# arduino-dice.net
KiCad netlist of a schematic drawn in EAGLE
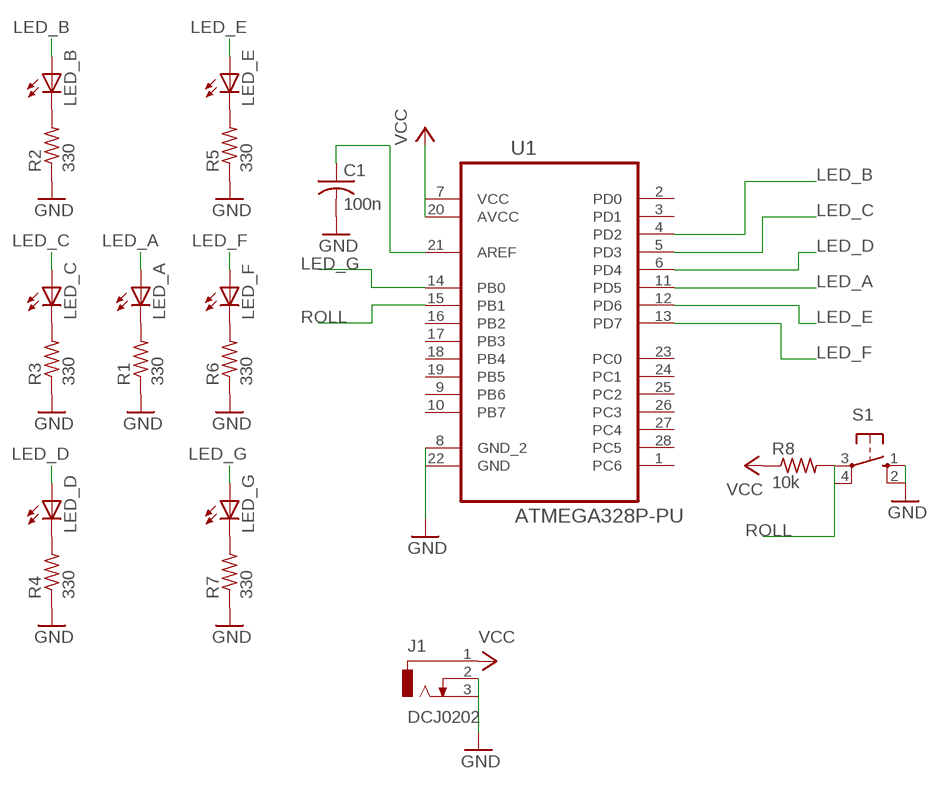
[diagram p0: schematic, sheet 1]

(export (version "E")
  (design (tool "Eeschema 10.0.6"))
  (components
    (comp (ref "C1")
      (value "100n")
      (footprint "eagle-import:C050-024X044")
      (libsource (lib "eagle-import") (part "C-US050-024X044"))
    )
    (comp (ref "J1")
      (value "DCJ0202")
      (footprint "eagle-import:DCJ0202")
      (libsource (lib "eagle-import") (part "DCJ0202"))
    )
    (comp (ref "LED_A")
      (value "LED5MM")
      (footprint "eagle-import:LED5MM")
      (libsource (lib "eagle-import") (part "LED5MM"))
    )
    (comp (ref "LED_B")
      (value "LED5MM")
      (footprint "eagle-import:LED5MM")
      (libsource (lib "eagle-import") (part "LED5MM"))
    )
    (comp (ref "LED_C")
      (value "LED5MM")
      (footprint "eagle-import:LED5MM")
      (libsource (lib "eagle-import") (part "LED5MM"))
    )
    (comp (ref "LED_D")
      (value "LED5MM")
      (footprint "eagle-import:LED5MM")
      (libsource (lib "eagle-import") (part "LED5MM"))
    )
    (comp (ref "LED_E")
      (value "LED5MM")
      (footprint "eagle-import:LED5MM")
      (libsource (lib "eagle-import") (part "LED5MM"))
    )
    (comp (ref "LED_F")
      (value "LED5MM")
      (footprint "eagle-import:LED5MM")
      (libsource (lib "eagle-import") (part "LED5MM"))
    )
    (comp (ref "LED_G")
      (value "LED5MM")
      (footprint "eagle-import:LED5MM")
      (libsource (lib "eagle-import") (part "LED5MM"))
    )
    (comp (ref "R1")
      (value "330")
      (footprint "eagle-import:0207_10")
      (libsource (lib "eagle-import") (part "R-US_0207/10"))
    )
    (comp (ref "R2")
      (value "330")
      (footprint "eagle-import:0207_10")
      (libsource (lib "eagle-import") (part "R-US_0207/10"))
    )
    (comp (ref "R3")
      (value "330")
      (footprint "eagle-import:0207_10")
      (libsource (lib "eagle-import") (part "R-US_0207/10"))
    )
    (comp (ref "R4")
      (value "330")
      (footprint "eagle-import:0207_10")
      (libsource (lib "eagle-import") (part "R-US_0207/10"))
    )
    (comp (ref "R5")
      (value "330")
      (footprint "eagle-import:0207_10")
      (libsource (lib "eagle-import") (part "R-US_0207/10"))
    )
    (comp (ref "R6")
      (value "330")
      (footprint "eagle-import:0207_10")
      (libsource (lib "eagle-import") (part "R-US_0207/10"))
    )
    (comp (ref "R7")
      (value "330")
      (footprint "eagle-import:0207_10")
      (libsource (lib "eagle-import") (part "R-US_0207/10"))
    )
    (comp (ref "R8")
      (value "10k")
      (footprint "eagle-import:0207_10")
      (libsource (lib "eagle-import") (part "R-US_0207/10"))
    )
    (comp (ref "S1")
      (value "10-XX")
      (footprint "eagle-import:B3F-10XX")
      (fields (field (name "MPN") "B3F-1000"))
      (libsource (lib "eagle-import") (part "10-XX"))
    )
    (comp (ref "U1")
      (value "ATMEGA328P-PU")
      (footprint "eagle-import:DIP254P762X457-28")
      (libsource (lib "eagle-import") (part "ATMEGA328P-PU"))
    )
  )
  (nets
    (net (code "1") (name "/LED_A") (class "Default")
      (node (ref "LED_A") (pin "A") (pinfunction "A_A") (pintype "passive"))
      (node (ref "U1") (pin "11") (pinfunction "PD5_11") (pintype "bidirectional"))
    )
    (net (code "2") (name "/LED_B") (class "Default")
      (node (ref "LED_B") (pin "A") (pinfunction "A_A") (pintype "passive"))
      (node (ref "U1") (pin "4") (pinfunction "PD2_4") (pintype "bidirectional"))
    )
    (net (code "3") (name "/LED_C") (class "Default")
      (node (ref "LED_C") (pin "A") (pinfunction "A_A") (pintype "passive"))
      (node (ref "U1") (pin "5") (pinfunction "PD3_5") (pintype "bidirectional"))
    )
    (net (code "4") (name "/LED_D") (class "Default")
      (node (ref "LED_D") (pin "A") (pinfunction "A_A") (pintype "passive"))
      (node (ref "U1") (pin "6") (pinfunction "PD4_6") (pintype "bidirectional"))
    )
    (net (code "5") (name "/LED_E") (class "Default")
      (node (ref "LED_E") (pin "A") (pinfunction "A_A") (pintype "passive"))
      (node (ref "U1") (pin "12") (pinfunction "PD6_12") (pintype "bidirectional"))
    )
    (net (code "6") (name "/LED_F") (class "Default")
      (node (ref "LED_F") (pin "A") (pinfunction "A_A") (pintype "passive"))
      (node (ref "U1") (pin "13") (pinfunction "PD7_13") (pintype "bidirectional"))
    )
    (net (code "7") (name "/LED_G") (class "Default")
      (node (ref "LED_G") (pin "A") (pinfunction "A_A") (pintype "passive"))
      (node (ref "U1") (pin "14") (pinfunction "PB0_14") (pintype "bidirectional"))
    )
    (net (code "8") (name "/ROLL") (class "Default")
      (node (ref "R8") (pin "2") (pinfunction "2_2") (pintype "passive"))
      (node (ref "S1") (pin "3") (pinfunction "P_3") (pintype "passive"))
      (node (ref "S1") (pin "4") (pinfunction "P1_4") (pintype "passive"))
      (node (ref "U1") (pin "15") (pinfunction "PB1_15") (pintype "bidirectional"))
    )
    (net (code "9") (name "GND") (class "Default")
      (node (ref "C1") (pin "2") (pinfunction "2_2") (pintype "passive"))
      (node (ref "J1") (pin "2") (pinfunction "2_2") (pintype "passive"))
      (node (ref "J1") (pin "3") (pinfunction "3_3") (pintype "passive"))
      (node (ref "R1") (pin "1") (pinfunction "1_1") (pintype "passive"))
      (node (ref "R2") (pin "1") (pinfunction "1_1") (pintype "passive"))
      (node (ref "R3") (pin "1") (pinfunction "1_1") (pintype "passive"))
      (node (ref "R4") (pin "1") (pinfunction "1_1") (pintype "passive"))
      (node (ref "R5") (pin "1") (pinfunction "1_1") (pintype "passive"))
      (node (ref "R6") (pin "1") (pinfunction "1_1") (pintype "passive"))
      (node (ref "R7") (pin "1") (pinfunction "1_1") (pintype "passive"))
      (node (ref "S1") (pin "1") (pinfunction "S_1") (pintype "passive"))
      (node (ref "S1") (pin "2") (pinfunction "S1_2") (pintype "passive"))
      (node (ref "U1") (pin "22") (pinfunction "GND_22") (pintype "passive"))
      (node (ref "U1") (pin "8") (pinfunction "GND_2_8") (pintype "passive"))
    )
    (net (code "10") (name "Net-(LED_A-C)") (class "Default")
      (node (ref "LED_A") (pin "K") (pinfunction "C_K") (pintype "passive"))
      (node (ref "R1") (pin "2") (pinfunction "2_2") (pintype "passive"))
    )
    (net (code "11") (name "Net-(LED_B-C)") (class "Default")
      (node (ref "LED_B") (pin "K") (pinfunction "C_K") (pintype "passive"))
      (node (ref "R2") (pin "2") (pinfunction "2_2") (pintype "passive"))
    )
    (net (code "12") (name "Net-(LED_C-C)") (class "Default")
      (node (ref "LED_C") (pin "K") (pinfunction "C_K") (pintype "passive"))
      (node (ref "R3") (pin "2") (pinfunction "2_2") (pintype "passive"))
    )
    (net (code "13") (name "Net-(LED_D-C)") (class "Default")
      (node (ref "LED_D") (pin "K") (pinfunction "C_K") (pintype "passive"))
      (node (ref "R4") (pin "2") (pinfunction "2_2") (pintype "passive"))
    )
    (net (code "14") (name "Net-(LED_E-C)") (class "Default")
      (node (ref "LED_E") (pin "K") (pinfunction "C_K") (pintype "passive"))
      (node (ref "R5") (pin "2") (pinfunction "2_2") (pintype "passive"))
    )
    (net (code "15") (name "Net-(LED_F-C)") (class "Default")
      (node (ref "LED_F") (pin "K") (pinfunction "C_K") (pintype "passive"))
      (node (ref "R6") (pin "2") (pinfunction "2_2") (pintype "passive"))
    )
    (net (code "16") (name "Net-(LED_G-C)") (class "Default")
      (node (ref "LED_G") (pin "K") (pinfunction "C_K") (pintype "passive"))
      (node (ref "R7") (pin "2") (pinfunction "2_2") (pintype "passive"))
    )
    (net (code "17") (name "Net-(U1-AREF)") (class "Default")
      (node (ref "C1") (pin "1") (pinfunction "1_1") (pintype "passive"))
      (node (ref "U1") (pin "21") (pinfunction "AREF_21") (pintype "input"))
    )
    (net (code "18") (name "VCC") (class "Default")
      (node (ref "J1") (pin "1") (pinfunction "1_1") (pintype "passive"))
      (node (ref "R8") (pin "1") (pinfunction "1_1") (pintype "passive"))
      (node (ref "U1") (pin "20") (pinfunction "AVCC_20") (pintype "power_in"))
      (node (ref "U1") (pin "7") (pinfunction "VCC_7") (pintype "power_in"))
    )
    (net (code "19") (name "unconnected-(U1-PB2-Pad16)") (class "Default")
      (node (ref "U1") (pin "16") (pinfunction "PB2_16") (pintype "bidirectional"))
    )
    (net (code "20") (name "unconnected-(U1-PB3-Pad17)") (class "Default")
      (node (ref "U1") (pin "17") (pinfunction "PB3_17") (pintype "bidirectional"))
    )
    (net (code "21") (name "unconnected-(U1-PB4-Pad18)") (class "Default")
      (node (ref "U1") (pin "18") (pinfunction "PB4_18") (pintype "bidirectional"))
    )
    (net (code "22") (name "unconnected-(U1-PB5-Pad19)") (class "Default")
      (node (ref "U1") (pin "19") (pinfunction "PB5_19") (pintype "bidirectional"))
    )
    (net (code "23") (name "unconnected-(U1-PB6-Pad9)") (class "Default")
      (node (ref "U1") (pin "9") (pinfunction "PB6_9") (pintype "bidirectional"))
    )
    (net (code "24") (name "unconnected-(U1-PB7-Pad10)") (class "Default")
      (node (ref "U1") (pin "10") (pinfunction "PB7_10") (pintype "bidirectional"))
    )
    (net (code "25") (name "unconnected-(U1-PC0-Pad23)") (class "Default")
      (node (ref "U1") (pin "23") (pinfunction "PC0_23") (pintype "bidirectional"))
    )
    (net (code "26") (name "unconnected-(U1-PC1-Pad24)") (class "Default")
      (node (ref "U1") (pin "24") (pinfunction "PC1_24") (pintype "bidirectional"))
    )
    (net (code "27") (name "unconnected-(U1-PC2-Pad25)") (class "Default")
      (node (ref "U1") (pin "25") (pinfunction "PC2_25") (pintype "bidirectional"))
    )
    (net (code "28") (name "unconnected-(U1-PC3-Pad26)") (class "Default")
      (node (ref "U1") (pin "26") (pinfunction "PC3_26") (pintype "bidirectional"))
    )
    (net (code "29") (name "unconnected-(U1-PC4-Pad27)") (class "Default")
      (node (ref "U1") (pin "27") (pinfunction "PC4_27") (pintype "bidirectional"))
    )
    (net (code "30") (name "unconnected-(U1-PC5-Pad28)") (class "Default")
      (node (ref "U1") (pin "28") (pinfunction "PC5_28") (pintype "bidirectional"))
    )
    (net (code "31") (name "unconnected-(U1-PC6-Pad1)") (class "Default")
      (node (ref "U1") (pin "1") (pinfunction "PC6_1") (pintype "bidirectional"))
    )
    (net (code "32") (name "unconnected-(U1-PD0-Pad2)") (class "Default")
      (node (ref "U1") (pin "2") (pinfunction "PD0_2") (pintype "bidirectional"))
    )
    (net (code "33") (name "unconnected-(U1-PD1-Pad3)") (class "Default")
      (node (ref "U1") (pin "3") (pinfunction "PD1_3") (pintype "bidirectional"))
    )
  )
)
